# pHORPBoard_V10.net
KiCad netlist of a schematic drawn in EAGLE
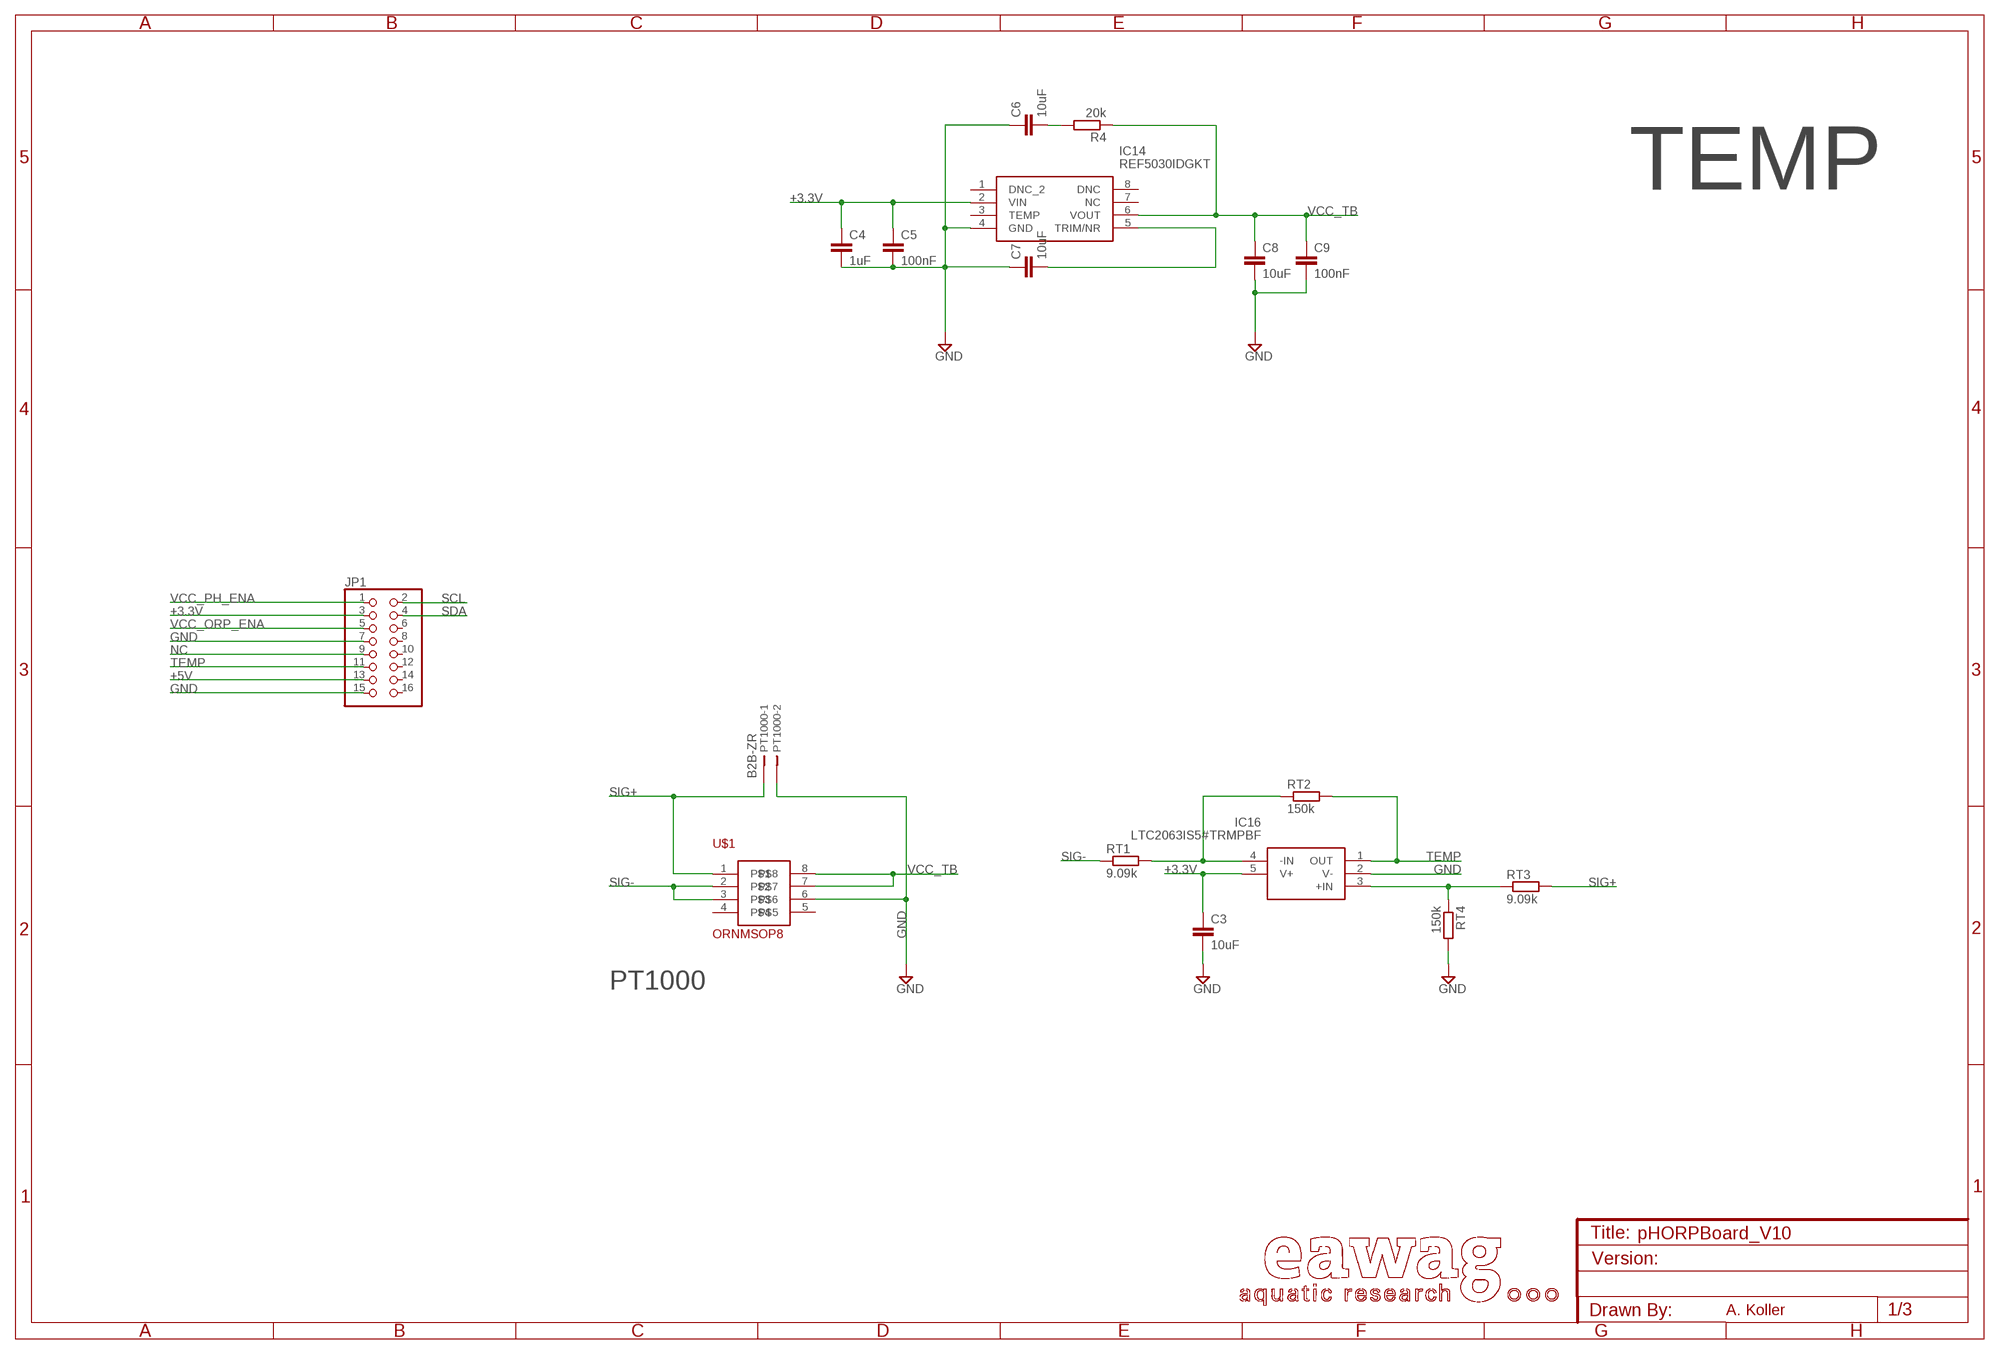
[diagram p0: schematic, sheet 1]
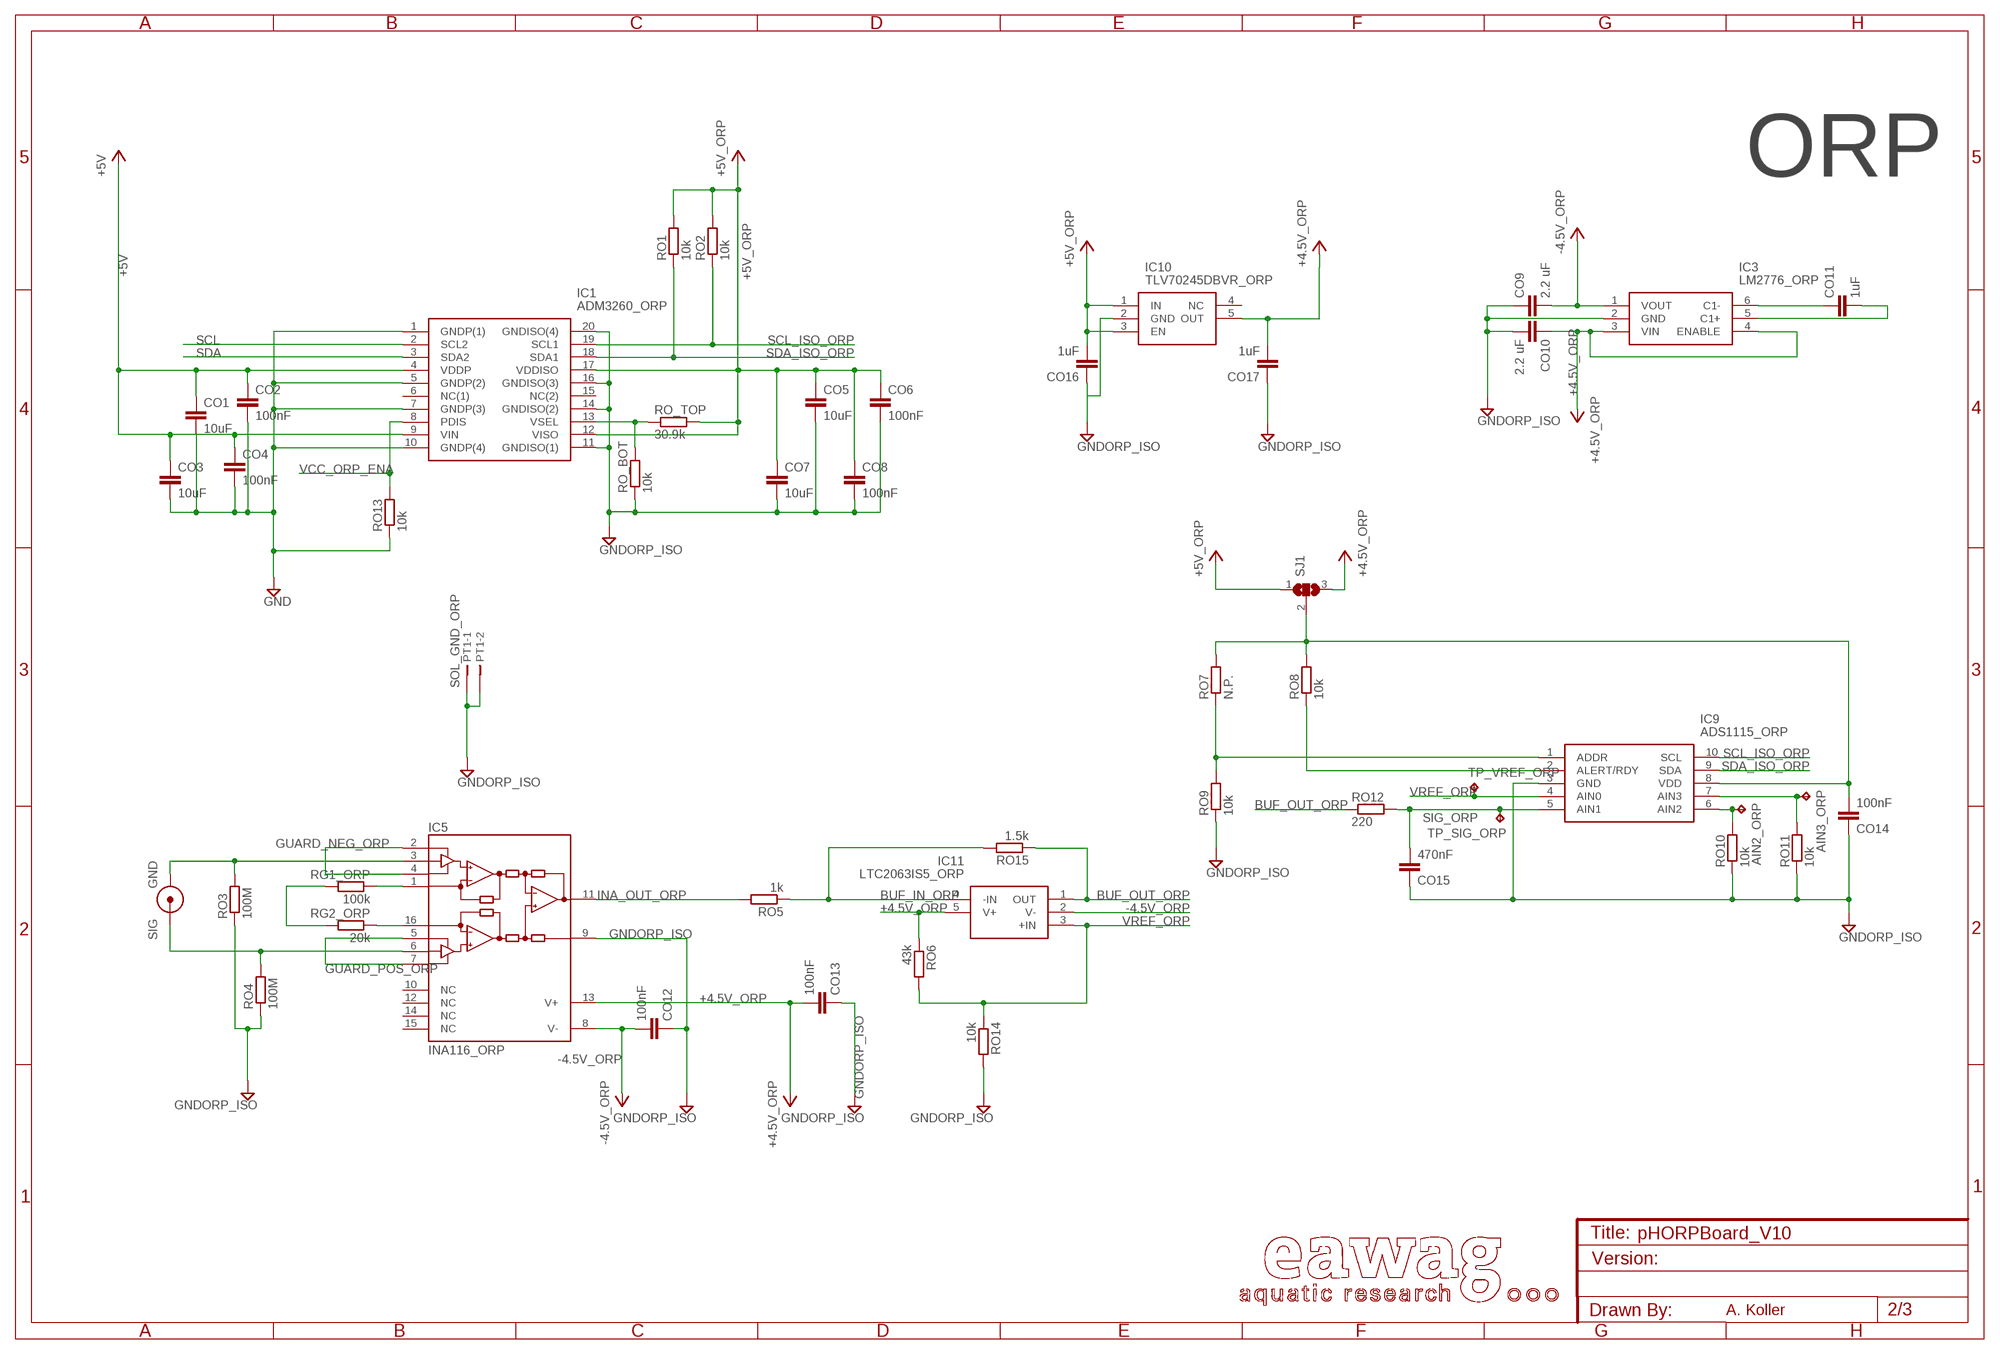
[diagram p1: schematic, sheet 2]
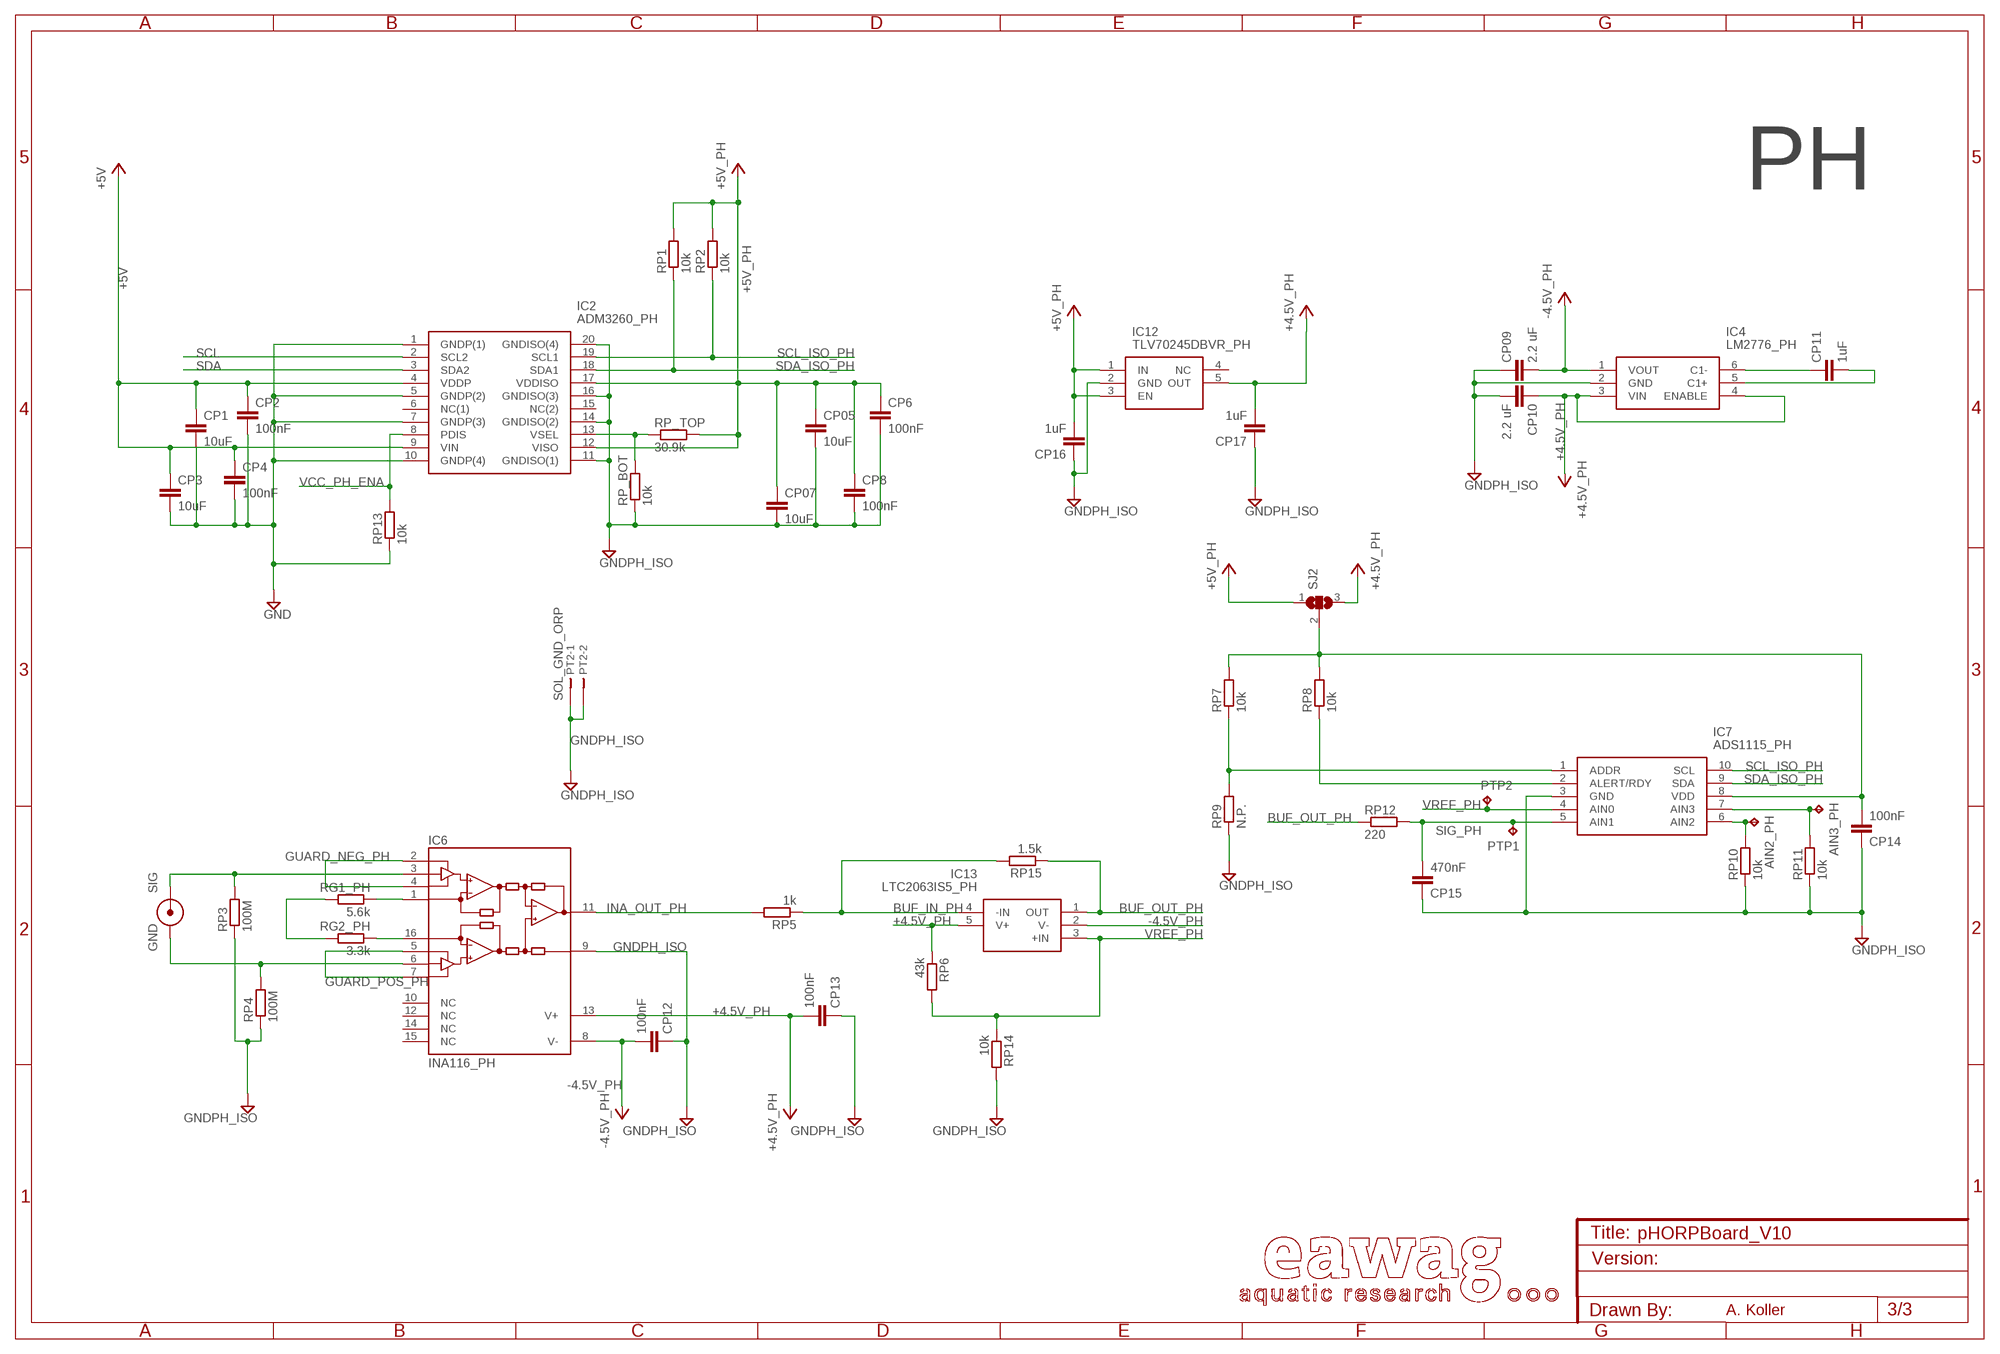
[diagram p2: schematic, sheet 3]

(export (version "E")
  (design (tool "Eeschema 10.0.6"))
  (components
    (comp (ref "C3")
      (value "10uF")
      (footprint "eagle-import:C0603")
      (libsource (lib "eagle-import") (part "C-EUC0603"))
    )
    (comp (ref "C4")
      (value "1uF")
      (footprint "eagle-import:C0603")
      (libsource (lib "eagle-import") (part "C-EUC0603"))
    )
    (comp (ref "C5")
      (value "100nF")
      (footprint "eagle-import:C0603")
      (libsource (lib "eagle-import") (part "C-EUC0603"))
    )
    (comp (ref "C6")
      (value "10uF")
      (footprint "eagle-import:C0603")
      (libsource (lib "eagle-import") (part "C-EUC0603"))
    )
    (comp (ref "C7")
      (value "10uF")
      (footprint "eagle-import:C0603")
      (libsource (lib "eagle-import") (part "C-EUC0603"))
    )
    (comp (ref "C8")
      (value "10uF")
      (footprint "eagle-import:C0603")
      (libsource (lib "eagle-import") (part "C-EUC0603"))
    )
    (comp (ref "C9")
      (value "100nF")
      (footprint "eagle-import:C0603")
      (libsource (lib "eagle-import") (part "C-EUC0603"))
    )
    (comp (ref "IC14")
      (value "REF5030IDGKT")
      (footprint "eagle-import:SOP65P490X110-8N")
      (libsource (lib "eagle-import") (part "REF5030IDGKT"))
    )
    (comp (ref "IC16")
      (value "LTC2063IS5#TRMPBF")
      (footprint "eagle-import:SOT95P280X100-5N")
      (libsource (lib "eagle-import") (part "LTC2063IS5#TRMPBF"))
    )
    (comp (ref "JP1")
      (value "PINHD-2X8")
      (footprint "eagle-import:2X08")
      (libsource (lib "eagle-import") (part "PINHD-2X8"))
    )
    (comp (ref "PT1000")
      (value "B2B-ZR")
      (footprint "eagle-import:B2B-ZR")
      (libsource (lib "eagle-import") (part "B2B-ZR"))
    )
    (comp (ref "R4")
      (value "20k")
      (footprint "eagle-import:R0603")
      (libsource (lib "eagle-import") (part "R-EU_R0603"))
    )
    (comp (ref "RT1")
      (value "9.09k")
      (footprint "eagle-import:R0603")
      (libsource (lib "eagle-import") (part "R-EU_R0603"))
    )
    (comp (ref "RT2")
      (value "150k")
      (footprint "eagle-import:R0603")
      (libsource (lib "eagle-import") (part "R-EU_R0603"))
    )
    (comp (ref "RT3")
      (value "9.09k")
      (footprint "eagle-import:R0603")
      (libsource (lib "eagle-import") (part "R-EU_R0603"))
    )
    (comp (ref "RT4")
      (value "150k")
      (footprint "eagle-import:R0603")
      (libsource (lib "eagle-import") (part "R-EU_R0603"))
    )
    (comp (ref "U$1")
      (value "ORNMSOP8")
      (footprint "eagle-import:MSOP8")
      (libsource (lib "eagle-import") (part "ORNMSOP8"))
    )
    (comp (ref "AIN2_ORP")
      (value "TPB1,27")
      (footprint "eagle-import:B1,27")
      (libsource (lib "eagle-import") (part "TPB1,27"))
    )
    (comp (ref "AIN3_ORP")
      (value "TPB1,27")
      (footprint "eagle-import:B1,27")
      (libsource (lib "eagle-import") (part "TPB1,27"))
    )
    (comp (ref "CO1")
      (value "10uF")
      (footprint "eagle-import:C0603")
      (libsource (lib "eagle-import") (part "C-EUC0603"))
    )
    (comp (ref "CO2")
      (value "100nF")
      (footprint "eagle-import:C0603")
      (libsource (lib "eagle-import") (part "rcl_C-EUC0603"))
    )
    (comp (ref "CO3")
      (value "10uF")
      (footprint "eagle-import:C0603")
      (libsource (lib "eagle-import") (part "C-EUC0603"))
    )
    (comp (ref "CO4")
      (value "100nF")
      (footprint "eagle-import:C0603")
      (libsource (lib "eagle-import") (part "rcl_C-EUC0603"))
    )
    (comp (ref "CO5")
      (value "10uF")
      (footprint "eagle-import:C0603")
      (libsource (lib "eagle-import") (part "rcl_C-EUC0603"))
    )
    (comp (ref "CO6")
      (value "100nF")
      (footprint "eagle-import:C0603")
      (libsource (lib "eagle-import") (part "rcl_C-EUC0603"))
    )
    (comp (ref "CO7")
      (value "10uF")
      (footprint "eagle-import:C0603")
      (libsource (lib "eagle-import") (part "C-EUC0603"))
    )
    (comp (ref "CO8")
      (value "100nF")
      (footprint "eagle-import:C0603")
      (libsource (lib "eagle-import") (part "rcl_C-EUC0603"))
    )
    (comp (ref "CO9")
      (value "2.2 uF")
      (footprint "eagle-import:C0603")
      (libsource (lib "eagle-import") (part "rcl_C-EUC0603"))
    )
    (comp (ref "CO10")
      (value "2.2 uF")
      (footprint "eagle-import:C0603")
      (libsource (lib "eagle-import") (part "rcl_C-EUC0603"))
    )
    (comp (ref "CO11")
      (value "1uF")
      (footprint "eagle-import:C0603")
      (libsource (lib "eagle-import") (part "rcl_C-EUC0603"))
    )
    (comp (ref "CO12")
      (value "100nF")
      (footprint "eagle-import:C0603")
      (libsource (lib "eagle-import") (part "rcl_C-EUC0603"))
    )
    (comp (ref "CO13")
      (value "100nF")
      (footprint "eagle-import:C0603")
      (libsource (lib "eagle-import") (part "rcl_C-EUC0603"))
    )
    (comp (ref "CO14")
      (value "100nF")
      (footprint "eagle-import:C0603")
      (libsource (lib "eagle-import") (part "rcl_C-EUC0603"))
    )
    (comp (ref "CO15")
      (value "470nF")
      (footprint "eagle-import:C0603")
      (libsource (lib "eagle-import") (part "rcl_C-EUC0603"))
    )
    (comp (ref "CO16")
      (value "1uF")
      (footprint "eagle-import:C0603")
      (libsource (lib "eagle-import") (part "rcl_C-EUC0603"))
    )
    (comp (ref "CO17")
      (value "1uF")
      (footprint "eagle-import:C0603")
      (libsource (lib "eagle-import") (part "rcl_C-EUC0603"))
    )
    (comp (ref "IC1")
      (value "ADM3260_ORP")
      (footprint "eagle-import:SOP65P780X200-20N")
      (fields (field (name "MANUFACTURER_PART_NUMBER") "ADM3260ARSZ-RL7"))
      (libsource (lib "eagle-import") (part "ADM3260ARSZ-RL7"))
    )
    (comp (ref "IC3")
      (value "LM2776_ORP")
      (footprint "eagle-import:SOT95P280X145-6N")
      (fields (field (name "MANUFACTURER_PART_NUMBER") "LM2776DBVT"))
      (libsource (lib "eagle-import") (part "LM2776DBVT"))
    )
    (comp (ref "IC5")
      (value "INA116_ORP")
      (footprint "eagle-import:SO16-1")
      (fields (field (name "MF") "TEXAS INSTRUMENTS") (field (name "MPN") "INA116UA"))
      (libsource (lib "eagle-import") (part "INA116U"))
    )
    (comp (ref "IC9")
      (value "ADS1115_ORP")
      (footprint "eagle-import:SOP50P490X110-10N")
      (fields
        (field (name "MANUFACTURER_PART_NUMBER") "ADS1115IDGST")
        (field (name "RS_PART_NUMBER") "9236911")
      )
      (libsource (lib "eagle-import") (part "ADS1115IDGST"))
    )
    (comp (ref "IC10")
      (value "TLV70245DBVR_ORP")
      (footprint "eagle-import:SOT95P280X145-5N")
      (fields (field (name "ARROW_PART_NUMBER") "TLV70245DBVR"))
      (libsource (lib "eagle-import") (part "TLV70245DBVR"))
    )
    (comp (ref "IC11")
      (value "LTC2063IS5_ORP")
      (footprint "eagle-import:SOT95P280X100-5N")
      (fields (field (name "ARROW_PART_NUMBER") "LTC2063IS5#TRMPBF"))
      (libsource (lib "eagle-import") (part "LTC2063IS5#TRMPBF"))
    )
    (comp (ref "ORP")
      (value "CON_HANNACON_HANNA_2")
      (footprint "eagle-import:CON_HANNA_2")
      (libsource (lib "eagle-import") (part "CON_HANNACON_HANNA_2"))
    )
    (comp (ref "PT1")
      (value "SOL_GND_ORP")
      (footprint "eagle-import:B2B-ZR")
      (libsource (lib "eagle-import") (part "B2B-ZR"))
    )
    (comp (ref "RG1_ORP")
      (value "100k")
      (footprint "eagle-import:R0603")
      (libsource (lib "eagle-import") (part "R-EU_R0603"))
    )
    (comp (ref "RG2_ORP")
      (value "20k")
      (footprint "eagle-import:R0603")
      (libsource (lib "eagle-import") (part "R-EU_R0603"))
    )
    (comp (ref "RO1")
      (value "10k")
      (footprint "eagle-import:R0603")
      (libsource (lib "eagle-import") (part "R-EU_R0603"))
    )
    (comp (ref "RO2")
      (value "10k")
      (footprint "eagle-import:R0603")
      (libsource (lib "eagle-import") (part "R-EU_R0603"))
    )
    (comp (ref "RO3")
      (value "100M")
      (footprint "eagle-import:R0603")
      (libsource (lib "eagle-import") (part "R-EU_R0603"))
    )
    (comp (ref "RO4")
      (value "100M")
      (footprint "eagle-import:R0603")
      (libsource (lib "eagle-import") (part "R-EU_R0603"))
    )
    (comp (ref "RO5")
      (value "1k")
      (footprint "eagle-import:R0603")
      (libsource (lib "eagle-import") (part "R-EU_R0603"))
    )
    (comp (ref "RO6")
      (value "43k")
      (footprint "eagle-import:R0603")
      (libsource (lib "eagle-import") (part "R-EU_R0603"))
    )
    (comp (ref "RO7")
      (value "N.P.")
      (footprint "eagle-import:R0603")
      (libsource (lib "eagle-import") (part "R-EU_R0603"))
    )
    (comp (ref "RO8")
      (value "10k")
      (footprint "eagle-import:R0603")
      (libsource (lib "eagle-import") (part "R-EU_R0603"))
    )
    (comp (ref "RO9")
      (value "10k")
      (footprint "eagle-import:R0603")
      (libsource (lib "eagle-import") (part "R-EU_R0603"))
    )
    (comp (ref "RO10")
      (value "10k")
      (footprint "eagle-import:R0603")
      (libsource (lib "eagle-import") (part "R-EU_R0603"))
    )
    (comp (ref "RO11")
      (value "10k")
      (footprint "eagle-import:R0603")
      (libsource (lib "eagle-import") (part "R-EU_R0603"))
    )
    (comp (ref "RO12")
      (value "220")
      (footprint "eagle-import:R0603")
      (libsource (lib "eagle-import") (part "R-EU_R0603"))
    )
    (comp (ref "RO13")
      (value "10k")
      (footprint "eagle-import:R0603")
      (libsource (lib "eagle-import") (part "R-EU_R0603"))
    )
    (comp (ref "RO14")
      (value "10k")
      (footprint "eagle-import:R0603")
      (libsource (lib "eagle-import") (part "R-EU_R0603"))
    )
    (comp (ref "RO15")
      (value "1.5k")
      (footprint "eagle-import:R0603")
      (libsource (lib "eagle-import") (part "R-EU_R0603"))
    )
    (comp (ref "RO_BOT")
      (value "10k")
      (footprint "eagle-import:R0603")
      (libsource (lib "eagle-import") (part "R-EU_R0603"))
    )
    (comp (ref "RO_TOP")
      (value "30.9k")
      (footprint "eagle-import:R0603")
      (libsource (lib "eagle-import") (part "R-EU_R0603"))
    )
    (comp (ref "SJ1")
      (value "SJ2W")
      (footprint "eagle-import:SJ_2")
      (libsource (lib "eagle-import") (part "SJ2W"))
    )
    (comp (ref "TP_SIG_ORP")
      (value "TPB1,27")
      (footprint "eagle-import:B1,27")
      (libsource (lib "eagle-import") (part "TPB1,27"))
    )
    (comp (ref "TP_VREF_ORP")
      (value "TPB1,27")
      (footprint "eagle-import:B1,27")
      (libsource (lib "eagle-import") (part "TPB1,27"))
    )
    (comp (ref "AIN2_PH")
      (value "TPB1,27")
      (footprint "eagle-import:B1,27")
      (libsource (lib "eagle-import") (part "TPB1,27"))
    )
    (comp (ref "AIN3_PH")
      (value "TPB1,27")
      (footprint "eagle-import:B1,27")
      (libsource (lib "eagle-import") (part "TPB1,27"))
    )
    (comp (ref "CP1")
      (value "10uF")
      (footprint "eagle-import:C0603")
      (libsource (lib "eagle-import") (part "C-EUC0603"))
    )
    (comp (ref "CP2")
      (value "100nF")
      (footprint "eagle-import:C0603")
      (libsource (lib "eagle-import") (part "rcl_C-EUC0603"))
    )
    (comp (ref "CP3")
      (value "10uF")
      (footprint "eagle-import:C0603")
      (libsource (lib "eagle-import") (part "C-EUC0603"))
    )
    (comp (ref "CP4")
      (value "100nF")
      (footprint "eagle-import:C0603")
      (libsource (lib "eagle-import") (part "rcl_C-EUC0603"))
    )
    (comp (ref "CP05")
      (value "10uF")
      (footprint "eagle-import:C0603")
      (libsource (lib "eagle-import") (part "C-EUC0603"))
    )
    (comp (ref "CP6")
      (value "100nF")
      (footprint "eagle-import:C0603")
      (libsource (lib "eagle-import") (part "rcl_C-EUC0603"))
    )
    (comp (ref "CP07")
      (value "10uF")
      (footprint "eagle-import:C0603")
      (libsource (lib "eagle-import") (part "C-EUC0603"))
    )
    (comp (ref "CP8")
      (value "100nF")
      (footprint "eagle-import:C0603")
      (libsource (lib "eagle-import") (part "rcl_C-EUC0603"))
    )
    (comp (ref "CP09")
      (value "2.2 uF")
      (footprint "eagle-import:C0603")
      (libsource (lib "eagle-import") (part "rcl_C-EUC0603"))
    )
    (comp (ref "CP10")
      (value "2.2 uF")
      (footprint "eagle-import:C0603")
      (libsource (lib "eagle-import") (part "C-EUC0603"))
    )
    (comp (ref "CP11")
      (value "1uF")
      (footprint "eagle-import:C0603")
      (libsource (lib "eagle-import") (part "rcl_C-EUC0603"))
    )
    (comp (ref "CP12")
      (value "100nF")
      (footprint "eagle-import:C0603")
      (libsource (lib "eagle-import") (part "rcl_C-EUC0603"))
    )
    (comp (ref "CP13")
      (value "100nF")
      (footprint "eagle-import:C0603")
      (libsource (lib "eagle-import") (part "rcl_C-EUC0603"))
    )
    (comp (ref "CP14")
      (value "100nF")
      (footprint "eagle-import:C0603")
      (libsource (lib "eagle-import") (part "rcl_C-EUC0603"))
    )
    (comp (ref "CP15")
      (value "470nF")
      (footprint "eagle-import:C0603")
      (libsource (lib "eagle-import") (part "rcl_C-EUC0603"))
    )
    (comp (ref "CP16")
      (value "1uF")
      (footprint "eagle-import:C0603")
      (libsource (lib "eagle-import") (part "rcl_C-EUC0603"))
    )
    (comp (ref "CP17")
      (value "1uF")
      (footprint "eagle-import:C0603")
      (libsource (lib "eagle-import") (part "rcl_C-EUC0603"))
    )
    (comp (ref "IC2")
      (value "ADM3260_PH")
      (footprint "eagle-import:SOP65P780X200-20N")
      (fields (field (name "MANUFACTURER_PART_NUMBER") "ADM3260ARSZ-RL7"))
      (libsource (lib "eagle-import") (part "ADM3260ARSZ-RL7"))
    )
    (comp (ref "IC4")
      (value "LM2776_PH")
      (footprint "eagle-import:SOT95P280X145-6N")
      (fields (field (name "MANUFACTURER_PART_NUMBER") "LM2776DBVT"))
      (libsource (lib "eagle-import") (part "LM2776DBVT"))
    )
    (comp (ref "IC6")
      (value "INA116_PH")
      (footprint "eagle-import:SO16-1")
      (fields (field (name "MF") "TEXAS INSTRUMENTS") (field (name "MPN") "INA116UA"))
      (libsource (lib "eagle-import") (part "INA116U"))
    )
    (comp (ref "IC7")
      (value "ADS1115_PH")
      (footprint "eagle-import:SOP50P490X110-10N")
      (fields
        (field (name "MANUFACTURER_PART_NUMBER") "ADS1115IDGST")
        (field (name "RS_PART_NUMBER") "9236911")
      )
      (libsource (lib "eagle-import") (part "ADS1115IDGST"))
    )
    (comp (ref "IC12")
      (value "TLV70245DBVR_PH")
      (footprint "eagle-import:SOT95P280X145-5N")
      (fields (field (name "ARROW_PART_NUMBER") "TLV70245DBVR"))
      (libsource (lib "eagle-import") (part "TLV70245DBVR"))
    )
    (comp (ref "IC13")
      (value "LTC2063IS5_PH")
      (footprint "eagle-import:SOT95P280X100-5N")
      (fields (field (name "ARROW_PART_NUMBER") "LTC2063IS5#TRMPBF"))
      (libsource (lib "eagle-import") (part "LTC2063IS5#TRMPBF"))
    )
    (comp (ref "PH")
      (value "CON_HANNA")
      (footprint "eagle-import:CON_HANNA")
      (libsource (lib "eagle-import") (part "CON_HANNA"))
    )
    (comp (ref "PT2")
      (value "SOL_GND_ORP")
      (footprint "eagle-import:B2B-ZR")
      (libsource (lib "eagle-import") (part "B2B-ZR"))
    )
    (comp (ref "PTP1")
      (value "TPB1,27")
      (footprint "eagle-import:B1,27")
      (libsource (lib "eagle-import") (part "TPB1,27"))
    )
    (comp (ref "PTP2")
      (value "TPB1,27")
      (footprint "eagle-import:B1,27")
      (libsource (lib "eagle-import") (part "TPB1,27"))
    )
    (comp (ref "RG1_PH")
      (value "5.6k")
      (footprint "eagle-import:R0603")
      (libsource (lib "eagle-import") (part "R-EU_R0603"))
    )
    (comp (ref "RG2_PH")
      (value "3.3k")
      (footprint "eagle-import:R0603")
      (libsource (lib "eagle-import") (part "R-EU_R0603"))
    )
    (comp (ref "RP1")
      (value "10k")
      (footprint "eagle-import:R0603")
      (libsource (lib "eagle-import") (part "R-EU_R0603"))
    )
    (comp (ref "RP2")
      (value "10k")
      (footprint "eagle-import:R0603")
      (libsource (lib "eagle-import") (part "R-EU_R0603"))
    )
    (comp (ref "RP3")
      (value "100M")
      (footprint "eagle-import:R0603")
      (libsource (lib "eagle-import") (part "R-EU_R0603"))
    )
    (comp (ref "RP4")
      (value "100M")
      (footprint "eagle-import:R0603")
      (libsource (lib "eagle-import") (part "R-EU_R0603"))
    )
    (comp (ref "RP5")
      (value "1k")
      (footprint "eagle-import:R0603")
      (libsource (lib "eagle-import") (part "R-EU_R0603"))
    )
    (comp (ref "RP6")
      (value "43k")
      (footprint "eagle-import:R0603")
      (libsource (lib "eagle-import") (part "R-EU_R0603"))
    )
    (comp (ref "RP7")
      (value "10k")
      (footprint "eagle-import:R0603")
      (libsource (lib "eagle-import") (part "R-EU_R0603"))
    )
    (comp (ref "RP8")
      (value "10k")
      (footprint "eagle-import:R0603")
      (libsource (lib "eagle-import") (part "R-EU_R0603"))
    )
    (comp (ref "RP9")
      (value "N.P.")
      (footprint "eagle-import:R0603")
      (libsource (lib "eagle-import") (part "R-EU_R0603"))
    )
    (comp (ref "RP10")
      (value "10k")
      (footprint "eagle-import:R0603")
      (libsource (lib "eagle-import") (part "R-EU_R0603"))
    )
    (comp (ref "RP11")
      (value "10k")
      (footprint "eagle-import:R0603")
      (libsource (lib "eagle-import") (part "R-EU_R0603"))
    )
    (comp (ref "RP12")
      (value "220")
      (footprint "eagle-import:R0603")
      (libsource (lib "eagle-import") (part "R-EU_R0603"))
    )
    (comp (ref "RP13")
      (value "10k")
      (footprint "eagle-import:R0603")
      (libsource (lib "eagle-import") (part "R-EU_R0603"))
    )
    (comp (ref "RP14")
      (value "10k")
      (footprint "eagle-import:R0603")
      (libsource (lib "eagle-import") (part "R-EU_R0603"))
    )
    (comp (ref "RP15")
      (value "1.5k")
      (footprint "eagle-import:R0603")
      (libsource (lib "eagle-import") (part "R-EU_R0603"))
    )
    (comp (ref "RP_BOT")
      (value "10k")
      (footprint "eagle-import:R0603")
      (libsource (lib "eagle-import") (part "R-EU_R0603"))
    )
    (comp (ref "RP_TOP")
      (value "30.9k")
      (footprint "eagle-import:R0603")
      (libsource (lib "eagle-import") (part "R-EU_R0603"))
    )
    (comp (ref "SJ2")
      (value "SJ2W")
      (footprint "eagle-import:SJ_2")
      (libsource (lib "eagle-import") (part "SJ2W"))
    )
  )
  (nets
    (net (code "1") (name "+3.3V") (class "Default")
      (node (ref "C3") (pin "1") (pinfunction "1_1") (pintype "passive"))
      (node (ref "C4") (pin "1") (pinfunction "1_1") (pintype "passive"))
      (node (ref "C5") (pin "1") (pinfunction "1_1") (pintype "passive"))
      (node (ref "IC14") (pin "2") (pinfunction "VIN_2") (pintype "bidirectional"))
      (node (ref "IC16") (pin "5") (pinfunction "V+_5") (pintype "power_in"))
      (node (ref "JP1") (pin "3") (pinfunction "3_3") (pintype "passive"))
    )
    (net (code "2") (name "+4.5V_ORP") (class "Default")
      (node (ref "CO10") (pin "1") (pinfunction "1_1") (pintype "passive"))
      (node (ref "CO13") (pin "2") (pinfunction "2_2") (pintype "passive"))
      (node (ref "CO17") (pin "2") (pinfunction "2_2") (pintype "passive"))
      (node (ref "IC10") (pin "5") (pinfunction "OUT_5") (pintype "output"))
      (node (ref "IC11") (pin "5") (pinfunction "V+_5") (pintype "power_in"))
      (node (ref "IC3") (pin "3") (pinfunction "VIN_3") (pintype "input"))
      (node (ref "IC3") (pin "4") (pinfunction "ENABLE_4") (pintype "input"))
      (node (ref "IC5") (pin "13") (pinfunction "V+_13") (pintype "power_in"))
      (node (ref "RO6") (pin "1") (pinfunction "1_1") (pintype "passive"))
      (node (ref "SJ1") (pin "3") (pinfunction "3_3") (pintype "passive"))
    )
    (net (code "3") (name "+4.5V_PH") (class "Default")
      (node (ref "CP10") (pin "1") (pinfunction "1_1") (pintype "passive"))
      (node (ref "CP13") (pin "2") (pinfunction "2_2") (pintype "passive"))
      (node (ref "CP17") (pin "2") (pinfunction "2_2") (pintype "passive"))
      (node (ref "IC12") (pin "5") (pinfunction "OUT_5") (pintype "output"))
      (node (ref "IC13") (pin "5") (pinfunction "V+_5") (pintype "power_in"))
      (node (ref "IC4") (pin "3") (pinfunction "VIN_3") (pintype "input"))
      (node (ref "IC4") (pin "4") (pinfunction "ENABLE_4") (pintype "input"))
      (node (ref "IC6") (pin "13") (pinfunction "V+_13") (pintype "power_in"))
      (node (ref "RP6") (pin "1") (pinfunction "1_1") (pintype "passive"))
      (node (ref "SJ2") (pin "3") (pinfunction "3_3") (pintype "passive"))
    )
    (net (code "4") (name "+5V") (class "Default")
      (node (ref "CO1") (pin "1") (pinfunction "1_1") (pintype "passive"))
      (node (ref "CO2") (pin "1") (pinfunction "1_1") (pintype "passive"))
      (node (ref "CO3") (pin "1") (pinfunction "1_1") (pintype "passive"))
      (node (ref "CO4") (pin "1") (pinfunction "1_1") (pintype "passive"))
      (node (ref "CP1") (pin "1") (pinfunction "1_1") (pintype "passive"))
      (node (ref "CP2") (pin "1") (pinfunction "1_1") (pintype "passive"))
      (node (ref "CP3") (pin "1") (pinfunction "1_1") (pintype "passive"))
      (node (ref "CP4") (pin "1") (pinfunction "1_1") (pintype "passive"))
      (node (ref "IC1") (pin "4") (pinfunction "VDDP_4") (pintype "input"))
      (node (ref "IC1") (pin "9") (pinfunction "VIN_9") (pintype "input"))
      (node (ref "IC2") (pin "4") (pinfunction "VDDP_4") (pintype "input"))
      (node (ref "IC2") (pin "9") (pinfunction "VIN_9") (pintype "input"))
      (node (ref "JP1") (pin "13") (pinfunction "13_13") (pintype "passive"))
    )
    (net (code "5") (name "+5V_ORP") (class "Default")
      (node (ref "CO16") (pin "2") (pinfunction "2_2") (pintype "passive"))
      (node (ref "CO5") (pin "1") (pinfunction "1_1") (pintype "passive"))
      (node (ref "CO6") (pin "1") (pinfunction "1_1") (pintype "passive"))
      (node (ref "CO7") (pin "1") (pinfunction "1_1") (pintype "passive"))
      (node (ref "CO8") (pin "1") (pinfunction "1_1") (pintype "passive"))
      (node (ref "IC1") (pin "12") (pinfunction "VISO_12") (pintype "input"))
      (node (ref "IC1") (pin "17") (pinfunction "VDDISO_17") (pintype "input"))
      (node (ref "IC10") (pin "1") (pinfunction "IN_1") (pintype "input"))
      (node (ref "IC10") (pin "3") (pinfunction "EN_3") (pintype "input"))
      (node (ref "RO1") (pin "2") (pinfunction "2_2") (pintype "passive"))
      (node (ref "RO2") (pin "2") (pinfunction "2_2") (pintype "passive"))
      (node (ref "RO_TOP") (pin "2") (pinfunction "2_2") (pintype "passive"))
      (node (ref "SJ1") (pin "1") (pinfunction "1_1") (pintype "passive"))
    )
    (net (code "6") (name "+5V_PH") (class "Default")
      (node (ref "CP05") (pin "1") (pinfunction "1_1") (pintype "passive"))
      (node (ref "CP07") (pin "1") (pinfunction "1_1") (pintype "passive"))
      (node (ref "CP16") (pin "2") (pinfunction "2_2") (pintype "passive"))
      (node (ref "CP6") (pin "1") (pinfunction "1_1") (pintype "passive"))
      (node (ref "CP8") (pin "1") (pinfunction "1_1") (pintype "passive"))
      (node (ref "IC12") (pin "1") (pinfunction "IN_1") (pintype "input"))
      (node (ref "IC12") (pin "3") (pinfunction "EN_3") (pintype "input"))
      (node (ref "IC2") (pin "12") (pinfunction "VISO_12") (pintype "input"))
      (node (ref "IC2") (pin "17") (pinfunction "VDDISO_17") (pintype "input"))
      (node (ref "RP1") (pin "2") (pinfunction "2_2") (pintype "passive"))
      (node (ref "RP2") (pin "2") (pinfunction "2_2") (pintype "passive"))
      (node (ref "RP_TOP") (pin "2") (pinfunction "2_2") (pintype "passive"))
      (node (ref "SJ2") (pin "1") (pinfunction "1_1") (pintype "passive"))
    )
    (net (code "7") (name "-4.5V_ORP") (class "Default")
      (node (ref "CO12") (pin "2") (pinfunction "2_2") (pintype "passive"))
      (node (ref "CO9") (pin "2") (pinfunction "2_2") (pintype "passive"))
      (node (ref "IC11") (pin "2") (pinfunction "V-_2") (pintype "power_in"))
      (node (ref "IC3") (pin "1") (pinfunction "VOUT_1") (pintype "input"))
      (node (ref "IC5") (pin "8") (pinfunction "V-_8") (pintype "power_in"))
    )
    (net (code "8") (name "-4.5V_PH") (class "Default")
      (node (ref "CP09") (pin "2") (pinfunction "2_2") (pintype "passive"))
      (node (ref "CP12") (pin "2") (pinfunction "2_2") (pintype "passive"))
      (node (ref "IC13") (pin "2") (pinfunction "V-_2") (pintype "power_in"))
      (node (ref "IC4") (pin "1") (pinfunction "VOUT_1") (pintype "input"))
      (node (ref "IC6") (pin "8") (pinfunction "V-_8") (pintype "power_in"))
    )
    (net (code "9") (name "BUF_IN_ORP") (class "Default")
      (node (ref "IC11") (pin "4") (pinfunction "-IN_4") (pintype "input"))
      (node (ref "RO15") (pin "2") (pinfunction "2_2") (pintype "passive"))
      (node (ref "RO5") (pin "1") (pinfunction "1_1") (pintype "passive"))
    )
    (net (code "10") (name "BUF_IN_PH") (class "Default")
      (node (ref "IC13") (pin "4") (pinfunction "-IN_4") (pintype "input"))
      (node (ref "RP15") (pin "2") (pinfunction "2_2") (pintype "passive"))
      (node (ref "RP5") (pin "1") (pinfunction "1_1") (pintype "passive"))
    )
    (net (code "11") (name "BUF_OUT_ORP") (class "Default")
      (node (ref "IC11") (pin "1") (pinfunction "OUT_1") (pintype "output"))
      (node (ref "RO12") (pin "1") (pinfunction "1_1") (pintype "passive"))
      (node (ref "RO15") (pin "1") (pinfunction "1_1") (pintype "passive"))
    )
    (net (code "12") (name "BUF_OUT_PH") (class "Default")
      (node (ref "IC13") (pin "1") (pinfunction "OUT_1") (pintype "output"))
      (node (ref "RP12") (pin "1") (pinfunction "1_1") (pintype "passive"))
      (node (ref "RP15") (pin "1") (pinfunction "1_1") (pintype "passive"))
    )
    (net (code "13") (name "GND") (class "Default")
      (node (ref "C3") (pin "2") (pinfunction "2_2") (pintype "passive"))
      (node (ref "C4") (pin "2") (pinfunction "2_2") (pintype "passive"))
      (node (ref "C5") (pin "2") (pinfunction "2_2") (pintype "passive"))
      (node (ref "C6") (pin "1") (pinfunction "1_1") (pintype "passive"))
      (node (ref "C7") (pin "1") (pinfunction "1_1") (pintype "passive"))
      (node (ref "C8") (pin "2") (pinfunction "2_2") (pintype "passive"))
      (node (ref "C9") (pin "2") (pinfunction "2_2") (pintype "passive"))
      (node (ref "CO1") (pin "2") (pinfunction "2_2") (pintype "passive"))
      (node (ref "CO2") (pin "2") (pinfunction "2_2") (pintype "passive"))
      (node (ref "CO3") (pin "2") (pinfunction "2_2") (pintype "passive"))
      (node (ref "CO4") (pin "2") (pinfunction "2_2") (pintype "passive"))
      (node (ref "CP1") (pin "2") (pinfunction "2_2") (pintype "passive"))
      (node (ref "CP2") (pin "2") (pinfunction "2_2") (pintype "passive"))
      (node (ref "CP3") (pin "2") (pinfunction "2_2") (pintype "passive"))
      (node (ref "CP4") (pin "2") (pinfunction "2_2") (pintype "passive"))
      (node (ref "IC1") (pin "1") (pinfunction "GNDP(1)_1") (pintype "input"))
      (node (ref "IC1") (pin "10") (pinfunction "GNDP(4)_10") (pintype "input"))
      (node (ref "IC1") (pin "5") (pinfunction "GNDP(2)_5") (pintype "input"))
      (node (ref "IC1") (pin "7") (pinfunction "GNDP(3)_7") (pintype "input"))
      (node (ref "IC14") (pin "4") (pinfunction "GND_4") (pintype "bidirectional"))
      (node (ref "IC16") (pin "2") (pinfunction "V-_2") (pintype "power_in"))
      (node (ref "IC2") (pin "1") (pinfunction "GNDP(1)_1") (pintype "input"))
      (node (ref "IC2") (pin "10") (pinfunction "GNDP(4)_10") (pintype "input"))
      (node (ref "IC2") (pin "5") (pinfunction "GNDP(2)_5") (pintype "input"))
      (node (ref "IC2") (pin "7") (pinfunction "GNDP(3)_7") (pintype "input"))
      (node (ref "JP1") (pin "15") (pinfunction "15_15") (pintype "passive"))
      (node (ref "JP1") (pin "7") (pinfunction "7_7") (pintype "passive"))
      (node (ref "PT1000") (pin "2") (pinfunction "1_2") (pintype "passive"))
      (node (ref "RO13") (pin "1") (pinfunction "1_1") (pintype "passive"))
      (node (ref "RP13") (pin "1") (pinfunction "1_1") (pintype "passive"))
      (node (ref "RT4") (pin "2") (pinfunction "2_2") (pintype "passive"))
      (node (ref "U$1") (pin "6") (pinfunction "P$6_6") (pintype "bidirectional"))
    )
    (net (code "14") (name "GNDORP_ISO") (class "Default")
      (node (ref "CO10") (pin "2") (pinfunction "2_2") (pintype "passive"))
      (node (ref "CO12") (pin "1") (pinfunction "1_1") (pintype "passive"))
      (node (ref "CO13") (pin "1") (pinfunction "1_1") (pintype "passive"))
      (node (ref "CO14") (pin "1") (pinfunction "1_1") (pintype "passive"))
      (node (ref "CO15") (pin "1") (pinfunction "1_1") (pintype "passive"))
      (node (ref "CO16") (pin "1") (pinfunction "1_1") (pintype "passive"))
      (node (ref "CO17") (pin "1") (pinfunction "1_1") (pintype "passive"))
      (node (ref "CO5") (pin "2") (pinfunction "2_2") (pintype "passive"))
      (node (ref "CO6") (pin "2") (pinfunction "2_2") (pintype "passive"))
      (node (ref "CO7") (pin "2") (pinfunction "2_2") (pintype "passive"))
      (node (ref "CO8") (pin "2") (pinfunction "2_2") (pintype "passive"))
      (node (ref "CO9") (pin "1") (pinfunction "1_1") (pintype "passive"))
      (node (ref "IC1") (pin "11") (pinfunction "GNDISO(1)_11") (pintype "input"))
      (node (ref "IC1") (pin "14") (pinfunction "GNDISO(2)_14") (pintype "input"))
      (node (ref "IC1") (pin "16") (pinfunction "GNDISO(3)_16") (pintype "input"))
      (node (ref "IC1") (pin "20") (pinfunction "GNDISO(4)_20") (pintype "input"))
      (node (ref "IC10") (pin "2") (pinfunction "GND_2") (pintype "power_in"))
      (node (ref "IC3") (pin "2") (pinfunction "GND_2") (pintype "input"))
      (node (ref "IC5") (pin "9") (pinfunction "REF_9") (pintype "passive"))
      (node (ref "IC9") (pin "3") (pinfunction "GND_3") (pintype "input"))
      (node (ref "PT1") (pin "1") (pinfunction "1_1") (pintype "passive"))
      (node (ref "PT1") (pin "2") (pinfunction "1_2") (pintype "passive"))
      (node (ref "RO10") (pin "1") (pinfunction "1_1") (pintype "passive"))
      (node (ref "RO11") (pin "1") (pinfunction "1_1") (pintype "passive"))
      (node (ref "RO14") (pin "2") (pinfunction "2_2") (pintype "passive"))
      (node (ref "RO3") (pin "1") (pinfunction "1_1") (pintype "passive"))
      (node (ref "RO4") (pin "1") (pinfunction "1_1") (pintype "passive"))
      (node (ref "RO9") (pin "1") (pinfunction "1_1") (pintype "passive"))
      (node (ref "RO_BOT") (pin "1") (pinfunction "1_1") (pintype "passive"))
    )
    (net (code "15") (name "GNDPH_ISO") (class "Default")
      (node (ref "CP05") (pin "2") (pinfunction "2_2") (pintype "passive"))
      (node (ref "CP07") (pin "2") (pinfunction "2_2") (pintype "passive"))
      (node (ref "CP09") (pin "1") (pinfunction "1_1") (pintype "passive"))
      (node (ref "CP10") (pin "2") (pinfunction "2_2") (pintype "passive"))
      (node (ref "CP12") (pin "1") (pinfunction "1_1") (pintype "passive"))
      (node (ref "CP13") (pin "1") (pinfunction "1_1") (pintype "passive"))
      (node (ref "CP14") (pin "1") (pinfunction "1_1") (pintype "passive"))
      (node (ref "CP15") (pin "1") (pinfunction "1_1") (pintype "passive"))
      (node (ref "CP16") (pin "1") (pinfunction "1_1") (pintype "passive"))
      (node (ref "CP17") (pin "1") (pinfunction "1_1") (pintype "passive"))
      (node (ref "CP6") (pin "2") (pinfunction "2_2") (pintype "passive"))
      (node (ref "CP8") (pin "2") (pinfunction "2_2") (pintype "passive"))
      (node (ref "IC12") (pin "2") (pinfunction "GND_2") (pintype "power_in"))
      (node (ref "IC2") (pin "11") (pinfunction "GNDISO(1)_11") (pintype "input"))
      (node (ref "IC2") (pin "14") (pinfunction "GNDISO(2)_14") (pintype "input"))
      (node (ref "IC2") (pin "16") (pinfunction "GNDISO(3)_16") (pintype "input"))
      (node (ref "IC2") (pin "20") (pinfunction "GNDISO(4)_20") (pintype "input"))
      (node (ref "IC4") (pin "2") (pinfunction "GND_2") (pintype "input"))
      (node (ref "IC6") (pin "9") (pinfunction "REF_9") (pintype "passive"))
      (node (ref "IC7") (pin "3") (pinfunction "GND_3") (pintype "input"))
      (node (ref "PT2") (pin "1") (pinfunction "1_1") (pintype "passive"))
      (node (ref "PT2") (pin "2") (pinfunction "1_2") (pintype "passive"))
      (node (ref "RP10") (pin "1") (pinfunction "1_1") (pintype "passive"))
      (node (ref "RP11") (pin "1") (pinfunction "1_1") (pintype "passive"))
      (node (ref "RP14") (pin "2") (pinfunction "2_2") (pintype "passive"))
      (node (ref "RP3") (pin "1") (pinfunction "1_1") (pintype "passive"))
      (node (ref "RP4") (pin "1") (pinfunction "1_1") (pintype "passive"))
      (node (ref "RP9") (pin "1") (pinfunction "1_1") (pintype "passive"))
      (node (ref "RP_BOT") (pin "1") (pinfunction "1_1") (pintype "passive"))
    )
    (net (code "16") (name "GUARD_NEG_ORP") (class "Default")
      (node (ref "IC5") (pin "2") (pinfunction "GUARD-_2") (pintype "passive"))
      (node (ref "IC5") (pin "4") (pinfunction "GUARD-_4") (pintype "passive"))
    )
    (net (code "17") (name "GUARD_NEG_PH") (class "Default")
      (node (ref "IC6") (pin "2") (pinfunction "GUARD-_2") (pintype "passive"))
      (node (ref "IC6") (pin "4") (pinfunction "GUARD-_4") (pintype "passive"))
    )
    (net (code "18") (name "GUARD_POS_ORP") (class "Default")
      (node (ref "IC5") (pin "5") (pinfunction "GUARD+_5") (pintype "passive"))
      (node (ref "IC5") (pin "7") (pinfunction "GUARD+_7") (pintype "passive"))
    )
    (net (code "19") (name "GUARD_POS_PH") (class "Default")
      (node (ref "IC6") (pin "5") (pinfunction "GUARD+_5") (pintype "passive"))
      (node (ref "IC6") (pin "7") (pinfunction "GUARD+_7") (pintype "passive"))
    )
    (net (code "20") (name "INA_OUT_ORP") (class "Default")
      (node (ref "IC5") (pin "11") (pinfunction "OUT_11") (pintype "output"))
      (node (ref "RO5") (pin "2") (pinfunction "2_2") (pintype "passive"))
    )
    (net (code "21") (name "INA_OUT_PH") (class "Default")
      (node (ref "IC6") (pin "11") (pinfunction "OUT_11") (pintype "output"))
      (node (ref "RP5") (pin "2") (pinfunction "2_2") (pintype "passive"))
    )
    (net (code "22") (name "NC") (class "Default")
      (node (ref "JP1") (pin "9") (pinfunction "9_9") (pintype "passive"))
    )
    (net (code "23") (name "Net-(C6-Pad2)") (class "Default")
      (node (ref "C6") (pin "2") (pinfunction "2_2") (pintype "passive"))
      (node (ref "R4") (pin "2") (pinfunction "2_2") (pintype "passive"))
    )
    (net (code "24") (name "Net-(IC1-VSEL)") (class "Default")
      (node (ref "IC1") (pin "13") (pinfunction "VSEL_13") (pintype "input"))
      (node (ref "RO_BOT") (pin "2") (pinfunction "2_2") (pintype "passive"))
      (node (ref "RO_TOP") (pin "1") (pinfunction "1_1") (pintype "passive"))
    )
    (net (code "25") (name "Net-(IC2-VSEL)") (class "Default")
      (node (ref "IC2") (pin "13") (pinfunction "VSEL_13") (pintype "input"))
      (node (ref "RP_BOT") (pin "2") (pinfunction "2_2") (pintype "passive"))
      (node (ref "RP_TOP") (pin "1") (pinfunction "1_1") (pintype "passive"))
    )
    (net (code "26") (name "Net-(IC3-C1+)") (class "Default")
      (node (ref "CO11") (pin "2") (pinfunction "2_2") (pintype "passive"))
      (node (ref "IC3") (pin "5") (pinfunction "C1+_5") (pintype "input"))
    )
    (net (code "27") (name "Net-(IC3-C1-)") (class "Default")
      (node (ref "CO11") (pin "1") (pinfunction "1_1") (pintype "passive"))
      (node (ref "IC3") (pin "6") (pinfunction "C1-_6") (pintype "input"))
    )
    (net (code "28") (name "Net-(IC4-C1+)") (class "Default")
      (node (ref "CP11") (pin "2") (pinfunction "2_2") (pintype "passive"))
      (node (ref "IC4") (pin "5") (pinfunction "C1+_5") (pintype "input"))
    )
    (net (code "29") (name "Net-(IC4-C1-)") (class "Default")
      (node (ref "CP11") (pin "1") (pinfunction "1_1") (pintype "passive"))
      (node (ref "IC4") (pin "6") (pinfunction "C1-_6") (pintype "input"))
    )
    (net (code "30") (name "Net-(IC5-+IN)") (class "Default")
      (node (ref "IC5") (pin "6") (pinfunction "+IN_6") (pintype "input"))
      (node (ref "ORP") (pin "CON_SIG") (pinfunction "CON_SIG_CON_SIG") (pintype "bidirectional"))
      (node (ref "RO4") (pin "2") (pinfunction "2_2") (pintype "passive"))
    )
    (net (code "31") (name "Net-(IC5--IN)") (class "Default")
      (node (ref "IC5") (pin "3") (pinfunction "-IN_3") (pintype "input"))
      (node (ref "ORP") (pin "CON_GND") (pinfunction "CON_GND_CON_GND") (pintype "bidirectional"))
      (node (ref "RO3") (pin "2") (pinfunction "2_2") (pintype "passive"))
    )
    (net (code "32") (name "Net-(IC5-RG-Pad1)") (class "Default")
      (node (ref "IC5") (pin "1") (pinfunction "RG_1") (pintype "passive"))
      (node (ref "RG1_ORP") (pin "1") (pinfunction "1_1") (pintype "passive"))
    )
    (net (code "33") (name "Net-(IC5-RG-Pad16)") (class "Default")
      (node (ref "IC5") (pin "16") (pinfunction "RG_16") (pintype "passive"))
      (node (ref "RG2_ORP") (pin "1") (pinfunction "1_1") (pintype "passive"))
    )
    (net (code "34") (name "Net-(IC6-+IN)") (class "Default")
      (node (ref "IC6") (pin "6") (pinfunction "+IN_6") (pintype "input"))
      (node (ref "PH") (pin "CON_GND") (pinfunction "CON_GND_CON_GND") (pintype "bidirectional"))
      (node (ref "RP4") (pin "2") (pinfunction "2_2") (pintype "passive"))
    )
    (net (code "35") (name "Net-(IC6--IN)") (class "Default")
      (node (ref "IC6") (pin "3") (pinfunction "-IN_3") (pintype "input"))
      (node (ref "PH") (pin "CON_SIG") (pinfunction "CON_SIG_CON_SIG") (pintype "bidirectional"))
      (node (ref "RP3") (pin "2") (pinfunction "2_2") (pintype "passive"))
    )
    (net (code "36") (name "Net-(IC6-RG-Pad1)") (class "Default")
      (node (ref "IC6") (pin "1") (pinfunction "RG_1") (pintype "passive"))
      (node (ref "RG1_PH") (pin "1") (pinfunction "1_1") (pintype "passive"))
    )
    (net (code "37") (name "Net-(IC6-RG-Pad16)") (class "Default")
      (node (ref "IC6") (pin "16") (pinfunction "RG_16") (pintype "passive"))
      (node (ref "RG2_PH") (pin "1") (pinfunction "1_1") (pintype "passive"))
    )
    (net (code "38") (name "Net-(IC7-ADDR)") (class "Default")
      (node (ref "IC7") (pin "1") (pinfunction "ADDR_1") (pintype "input"))
      (node (ref "RP7") (pin "1") (pinfunction "1_1") (pintype "passive"))
      (node (ref "RP9") (pin "2") (pinfunction "2_2") (pintype "passive"))
    )
    (net (code "39") (name "Net-(IC7-AIN2)") (class "Default")
      (node (ref "AIN2_PH") (pin "TP") (pinfunction "TP_TP") (pintype "input"))
      (node (ref "IC7") (pin "6") (pinfunction "AIN2_6") (pintype "input"))
      (node (ref "RP10") (pin "2") (pinfunction "2_2") (pintype "passive"))
    )
    (net (code "40") (name "Net-(IC7-AIN3)") (class "Default")
      (node (ref "AIN3_PH") (pin "TP") (pinfunction "TP_TP") (pintype "input"))
      (node (ref "IC7") (pin "7") (pinfunction "AIN3_7") (pintype "input"))
      (node (ref "RP11") (pin "2") (pinfunction "2_2") (pintype "passive"))
    )
    (net (code "41") (name "Net-(IC7-ALERT{slash}RDY)") (class "Default")
      (node (ref "IC7") (pin "2") (pinfunction "ALERT/RDY_2") (pintype "input"))
      (node (ref "RP8") (pin "1") (pinfunction "1_1") (pintype "passive"))
    )
    (net (code "42") (name "Net-(IC7-VDD)") (class "Default")
      (node (ref "CP14") (pin "2") (pinfunction "2_2") (pintype "passive"))
      (node (ref "IC7") (pin "8") (pinfunction "VDD_8") (pintype "input"))
      (node (ref "RP7") (pin "2") (pinfunction "2_2") (pintype "passive"))
      (node (ref "RP8") (pin "2") (pinfunction "2_2") (pintype "passive"))
      (node (ref "SJ2") (pin "2") (pinfunction "2_2") (pintype "passive"))
    )
    (net (code "43") (name "Net-(IC9-ADDR)") (class "Default")
      (node (ref "IC9") (pin "1") (pinfunction "ADDR_1") (pintype "input"))
      (node (ref "RO7") (pin "1") (pinfunction "1_1") (pintype "passive"))
      (node (ref "RO9") (pin "2") (pinfunction "2_2") (pintype "passive"))
    )
    (net (code "44") (name "Net-(IC9-AIN2)") (class "Default")
      (node (ref "AIN2_ORP") (pin "TP") (pinfunction "TP_TP") (pintype "input"))
      (node (ref "IC9") (pin "6") (pinfunction "AIN2_6") (pintype "input"))
      (node (ref "RO10") (pin "2") (pinfunction "2_2") (pintype "passive"))
    )
    (net (code "45") (name "Net-(IC9-AIN3)") (class "Default")
      (node (ref "AIN3_ORP") (pin "TP") (pinfunction "TP_TP") (pintype "input"))
      (node (ref "IC9") (pin "7") (pinfunction "AIN3_7") (pintype "input"))
      (node (ref "RO11") (pin "2") (pinfunction "2_2") (pintype "passive"))
    )
    (net (code "46") (name "Net-(IC9-ALERT{slash}RDY)") (class "Default")
      (node (ref "IC9") (pin "2") (pinfunction "ALERT/RDY_2") (pintype "input"))
      (node (ref "RO8") (pin "1") (pinfunction "1_1") (pintype "passive"))
    )
    (net (code "47") (name "Net-(IC9-VDD)") (class "Default")
      (node (ref "CO14") (pin "2") (pinfunction "2_2") (pintype "passive"))
      (node (ref "IC9") (pin "8") (pinfunction "VDD_8") (pintype "input"))
      (node (ref "RO7") (pin "2") (pinfunction "2_2") (pintype "passive"))
      (node (ref "RO8") (pin "2") (pinfunction "2_2") (pintype "passive"))
      (node (ref "SJ1") (pin "2") (pinfunction "2_2") (pintype "passive"))
    )
    (net (code "48") (name "Net-(IC14-TRIM{slash}NR)") (class "Default")
      (node (ref "C7") (pin "2") (pinfunction "2_2") (pintype "passive"))
      (node (ref "IC14") (pin "5") (pinfunction "TRIM/NR_5") (pintype "bidirectional"))
    )
    (net (code "49") (name "Net-(IC16-+IN)") (class "Default")
      (node (ref "IC16") (pin "3") (pinfunction "+IN_3") (pintype "input"))
      (node (ref "RT3") (pin "1") (pinfunction "1_1") (pintype "passive"))
      (node (ref "RT4") (pin "1") (pinfunction "1_1") (pintype "passive"))
    )
    (net (code "50") (name "Net-(IC16--IN)") (class "Default")
      (node (ref "IC16") (pin "4") (pinfunction "-IN_4") (pintype "input"))
      (node (ref "RT1") (pin "2") (pinfunction "2_2") (pintype "passive"))
      (node (ref "RT2") (pin "1") (pinfunction "1_1") (pintype "passive"))
    )
    (net (code "51") (name "Net-(RG1_ORP-Pad2)") (class "Default")
      (node (ref "RG1_ORP") (pin "2") (pinfunction "2_2") (pintype "passive"))
      (node (ref "RG2_ORP") (pin "2") (pinfunction "2_2") (pintype "passive"))
    )
    (net (code "52") (name "Net-(RG1_PH-Pad2)") (class "Default")
      (node (ref "RG1_PH") (pin "2") (pinfunction "2_2") (pintype "passive"))
      (node (ref "RG2_PH") (pin "2") (pinfunction "2_2") (pintype "passive"))
    )
    (net (code "53") (name "SCL") (class "Default")
      (node (ref "IC1") (pin "2") (pinfunction "SCL2_2") (pintype "input"))
      (node (ref "IC2") (pin "2") (pinfunction "SCL2_2") (pintype "input"))
      (node (ref "JP1") (pin "2") (pinfunction "2_2") (pintype "passive"))
    )
    (net (code "54") (name "SCL_ISO_ORP") (class "Default")
      (node (ref "IC1") (pin "19") (pinfunction "SCL1_19") (pintype "input"))
      (node (ref "IC9") (pin "10") (pinfunction "SCL_10") (pintype "input"))
      (node (ref "RO2") (pin "1") (pinfunction "1_1") (pintype "passive"))
    )
    (net (code "55") (name "SCL_ISO_PH") (class "Default")
      (node (ref "IC2") (pin "19") (pinfunction "SCL1_19") (pintype "input"))
      (node (ref "IC7") (pin "10") (pinfunction "SCL_10") (pintype "input"))
      (node (ref "RP2") (pin "1") (pinfunction "1_1") (pintype "passive"))
    )
    (net (code "56") (name "SDA") (class "Default")
      (node (ref "IC1") (pin "3") (pinfunction "SDA2_3") (pintype "input"))
      (node (ref "IC2") (pin "3") (pinfunction "SDA2_3") (pintype "input"))
      (node (ref "JP1") (pin "4") (pinfunction "4_4") (pintype "passive"))
    )
    (net (code "57") (name "SDA_ISO_ORP") (class "Default")
      (node (ref "IC1") (pin "18") (pinfunction "SDA1_18") (pintype "input"))
      (node (ref "IC9") (pin "9") (pinfunction "SDA_9") (pintype "input"))
      (node (ref "RO1") (pin "1") (pinfunction "1_1") (pintype "passive"))
    )
    (net (code "58") (name "SDA_ISO_PH") (class "Default")
      (node (ref "IC2") (pin "18") (pinfunction "SDA1_18") (pintype "input"))
      (node (ref "IC7") (pin "9") (pinfunction "SDA_9") (pintype "input"))
      (node (ref "RP1") (pin "1") (pinfunction "1_1") (pintype "passive"))
    )
    (net (code "59") (name "SIG+") (class "Default")
      (node (ref "PT1000") (pin "1") (pinfunction "1_1") (pintype "passive"))
      (node (ref "RT3") (pin "2") (pinfunction "2_2") (pintype "passive"))
      (node (ref "U$1") (pin "1") (pinfunction "P$1_1") (pintype "bidirectional"))
    )
    (net (code "60") (name "SIG-") (class "Default")
      (node (ref "RT1") (pin "1") (pinfunction "1_1") (pintype "passive"))
      (node (ref "U$1") (pin "2") (pinfunction "P$2_2") (pintype "bidirectional"))
      (node (ref "U$1") (pin "3") (pinfunction "P$3_3") (pintype "bidirectional"))
    )
    (net (code "61") (name "SIG_ORP") (class "Default")
      (node (ref "CO15") (pin "2") (pinfunction "2_2") (pintype "passive"))
      (node (ref "IC9") (pin "5") (pinfunction "AIN1_5") (pintype "input"))
      (node (ref "RO12") (pin "2") (pinfunction "2_2") (pintype "passive"))
      (node (ref "TP_SIG_ORP") (pin "TP") (pinfunction "TP_TP") (pintype "input"))
    )
    (net (code "62") (name "SIG_PH") (class "Default")
      (node (ref "CP15") (pin "2") (pinfunction "2_2") (pintype "passive"))
      (node (ref "IC7") (pin "5") (pinfunction "AIN1_5") (pintype "input"))
      (node (ref "PTP1") (pin "TP") (pinfunction "TP_TP") (pintype "input"))
      (node (ref "RP12") (pin "2") (pinfunction "2_2") (pintype "passive"))
    )
    (net (code "63") (name "TEMP") (class "Default")
      (node (ref "IC16") (pin "1") (pinfunction "OUT_1") (pintype "output"))
      (node (ref "JP1") (pin "11") (pinfunction "11_11") (pintype "passive"))
      (node (ref "RT2") (pin "2") (pinfunction "2_2") (pintype "passive"))
    )
    (net (code "64") (name "VCC_ORP_ENA") (class "Default")
      (node (ref "IC1") (pin "8") (pinfunction "PDIS_8") (pintype "input"))
      (node (ref "JP1") (pin "5") (pinfunction "5_5") (pintype "passive"))
      (node (ref "RO13") (pin "2") (pinfunction "2_2") (pintype "passive"))
    )
    (net (code "65") (name "VCC_PH_ENA") (class "Default")
      (node (ref "IC2") (pin "8") (pinfunction "PDIS_8") (pintype "input"))
      (node (ref "JP1") (pin "1") (pinfunction "1_1") (pintype "passive"))
      (node (ref "RP13") (pin "2") (pinfunction "2_2") (pintype "passive"))
    )
    (net (code "66") (name "VCC_TB") (class "Default")
      (node (ref "C8") (pin "1") (pinfunction "1_1") (pintype "passive"))
      (node (ref "C9") (pin "1") (pinfunction "1_1") (pintype "passive"))
      (node (ref "IC14") (pin "6") (pinfunction "VOUT_6") (pintype "bidirectional"))
      (node (ref "R4") (pin "1") (pinfunction "1_1") (pintype "passive"))
      (node (ref "U$1") (pin "7") (pinfunction "P$7_7") (pintype "bidirectional"))
      (node (ref "U$1") (pin "8") (pinfunction "P$8_8") (pintype "bidirectional"))
    )
    (net (code "67") (name "VREF_ORP") (class "Default")
      (node (ref "IC11") (pin "3") (pinfunction "+IN_3") (pintype "input"))
      (node (ref "IC9") (pin "4") (pinfunction "AIN0_4") (pintype "input"))
      (node (ref "RO14") (pin "1") (pinfunction "1_1") (pintype "passive"))
      (node (ref "RO6") (pin "2") (pinfunction "2_2") (pintype "passive"))
      (node (ref "TP_VREF_ORP") (pin "TP") (pinfunction "TP_TP") (pintype "input"))
    )
    (net (code "68") (name "VREF_PH") (class "Default")
      (node (ref "IC13") (pin "3") (pinfunction "+IN_3") (pintype "input"))
      (node (ref "IC7") (pin "4") (pinfunction "AIN0_4") (pintype "input"))
      (node (ref "PTP2") (pin "TP") (pinfunction "TP_TP") (pintype "input"))
      (node (ref "RP14") (pin "1") (pinfunction "1_1") (pintype "passive"))
      (node (ref "RP6") (pin "2") (pinfunction "2_2") (pintype "passive"))
    )
    (net (code "69") (name "unconnected-(IC1-NC(1)-Pad6)") (class "Default")
      (node (ref "IC1") (pin "6") (pinfunction "NC(1)_6") (pintype "input"))
    )
    (net (code "70") (name "unconnected-(IC1-NC(2)-Pad15)") (class "Default")
      (node (ref "IC1") (pin "15") (pinfunction "NC(2)_15") (pintype "input"))
    )
    (net (code "71") (name "unconnected-(IC2-NC(1)-Pad6)") (class "Default")
      (node (ref "IC2") (pin "6") (pinfunction "NC(1)_6") (pintype "input"))
    )
    (net (code "72") (name "unconnected-(IC2-NC(2)-Pad15)") (class "Default")
      (node (ref "IC2") (pin "15") (pinfunction "NC(2)_15") (pintype "input"))
    )
    (net (code "73") (name "unconnected-(IC5-NC-Pad10)") (class "Default")
      (node (ref "IC5") (pin "10") (pinfunction "NC_10") (pintype "no_connect"))
    )
    (net (code "74") (name "unconnected-(IC5-NC-Pad12)") (class "Default")
      (node (ref "IC5") (pin "12") (pinfunction "NC_12") (pintype "no_connect"))
    )
    (net (code "75") (name "unconnected-(IC5-NC-Pad14)") (class "Default")
      (node (ref "IC5") (pin "14") (pinfunction "NC_14") (pintype "no_connect"))
    )
    (net (code "76") (name "unconnected-(IC5-NC-Pad15)") (class "Default")
      (node (ref "IC5") (pin "15") (pinfunction "NC_15") (pintype "no_connect"))
    )
    (net (code "77") (name "unconnected-(IC6-NC-Pad10)") (class "Default")
      (node (ref "IC6") (pin "10") (pinfunction "NC_10") (pintype "no_connect"))
    )
    (net (code "78") (name "unconnected-(IC6-NC-Pad12)") (class "Default")
      (node (ref "IC6") (pin "12") (pinfunction "NC_12") (pintype "no_connect"))
    )
    (net (code "79") (name "unconnected-(IC6-NC-Pad14)") (class "Default")
      (node (ref "IC6") (pin "14") (pinfunction "NC_14") (pintype "no_connect"))
    )
    (net (code "80") (name "unconnected-(IC6-NC-Pad15)") (class "Default")
      (node (ref "IC6") (pin "15") (pinfunction "NC_15") (pintype "no_connect"))
    )
    (net (code "81") (name "unconnected-(IC10-NC-Pad4)") (class "Default")
      (node (ref "IC10") (pin "4") (pinfunction "NC_4") (pintype "no_connect"))
    )
    (net (code "82") (name "unconnected-(IC12-NC-Pad4)") (class "Default")
      (node (ref "IC12") (pin "4") (pinfunction "NC_4") (pintype "no_connect"))
    )
    (net (code "83") (name "unconnected-(IC14-DNC-Pad8)") (class "Default")
      (node (ref "IC14") (pin "8") (pinfunction "DNC_8") (pintype "bidirectional"))
    )
    (net (code "84") (name "unconnected-(IC14-DNC_2-Pad1)") (class "Default")
      (node (ref "IC14") (pin "1") (pinfunction "DNC_2_1") (pintype "bidirectional"))
    )
    (net (code "85") (name "unconnected-(IC14-NC-Pad7)") (class "Default")
      (node (ref "IC14") (pin "7") (pinfunction "NC_7") (pintype "no_connect"))
    )
    (net (code "86") (name "unconnected-(IC14-TEMP-Pad3)") (class "Default")
      (node (ref "IC14") (pin "3") (pinfunction "TEMP_3") (pintype "bidirectional"))
    )
    (net (code "87") (name "unconnected-(JP1-Pad6)") (class "Default")
      (node (ref "JP1") (pin "6") (pinfunction "6_6") (pintype "passive"))
    )
    (net (code "88") (name "unconnected-(JP1-Pad8)") (class "Default")
      (node (ref "JP1") (pin "8") (pinfunction "8_8") (pintype "passive"))
    )
    (net (code "89") (name "unconnected-(JP1-Pad10)") (class "Default")
      (node (ref "JP1") (pin "10") (pinfunction "10_10") (pintype "passive"))
    )
    (net (code "90") (name "unconnected-(JP1-Pad12)") (class "Default")
      (node (ref "JP1") (pin "12") (pinfunction "12_12") (pintype "passive"))
    )
    (net (code "91") (name "unconnected-(JP1-Pad14)") (class "Default")
      (node (ref "JP1") (pin "14") (pinfunction "14_14") (pintype "passive"))
    )
    (net (code "92") (name "unconnected-(JP1-Pad16)") (class "Default")
      (node (ref "JP1") (pin "16") (pinfunction "16_16") (pintype "passive"))
    )
    (net (code "93") (name "unconnected-(U$1-P$4-Pad4)") (class "Default")
      (node (ref "U$1") (pin "4") (pinfunction "P$4_4") (pintype "bidirectional"))
    )
    (net (code "94") (name "unconnected-(U$1-P$5-Pad5)") (class "Default")
      (node (ref "U$1") (pin "5") (pinfunction "P$5_5") (pintype "bidirectional"))
    )
  )
)
